# main.net
KiCad netlist of a schematic drawn in EAGLE
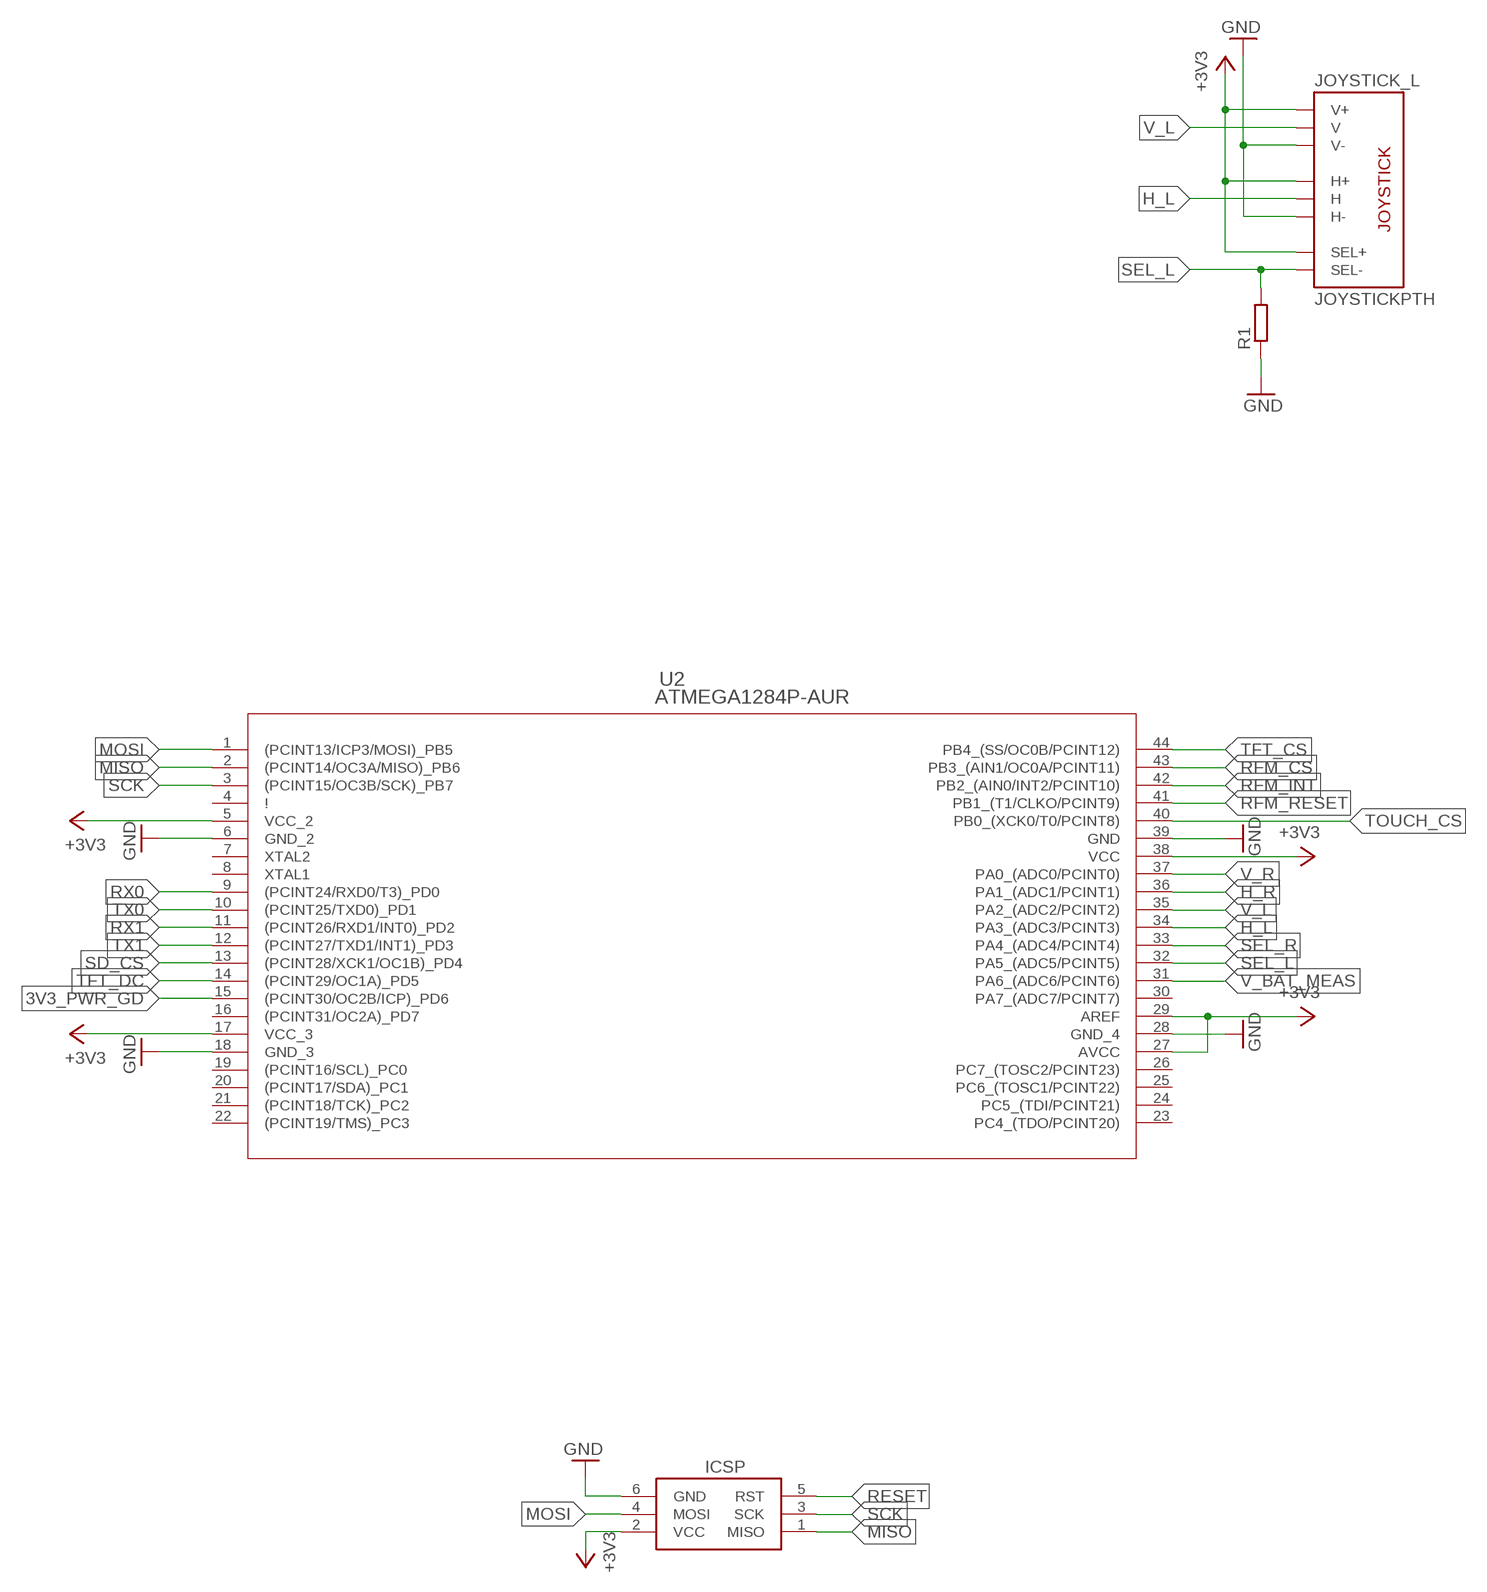
[diagram p0: schematic, sheet 1, part 1 of 2]
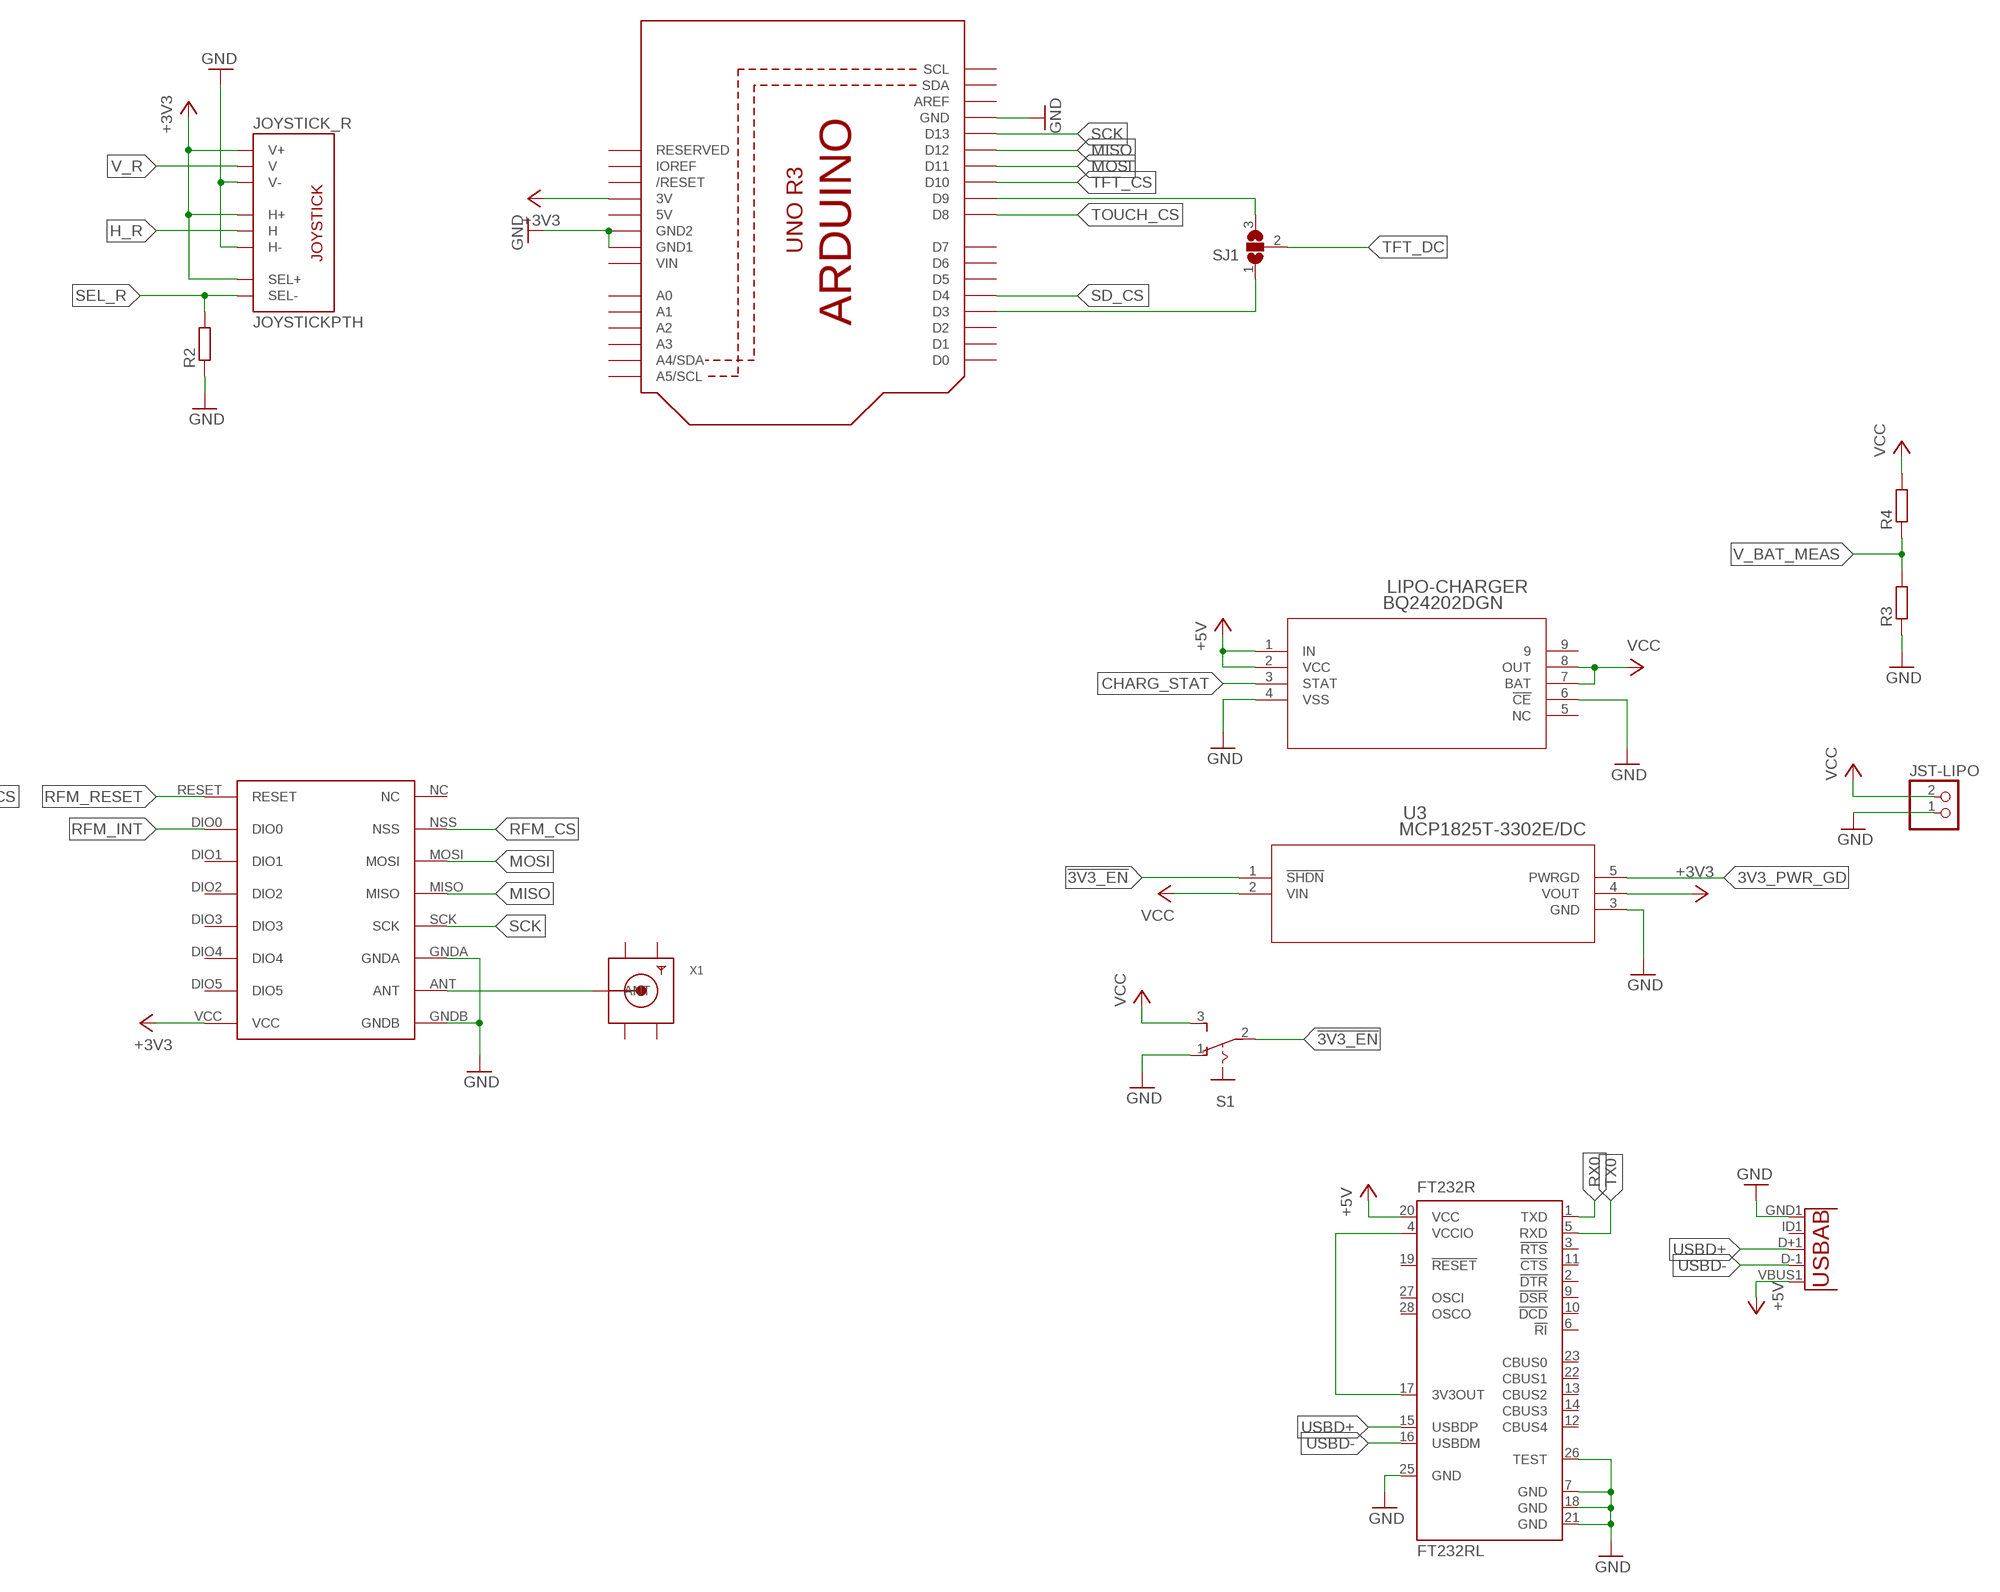
[diagram p1: schematic, sheet 1, part 2 of 2]

(export (version "E")
  (design (tool "Eeschema 10.0.6"))
  (components
    (comp (ref "FT232R")
      (value "FT232RL")
      (footprint "eagle-import:SSOP28")
      (libsource (lib "eagle-import") (part "FT232RL"))
    )
    (comp (ref "ICSP")
      (value "AVRISP-BOX")
      (footprint "eagle-import:AVRISP-BOX")
      (libsource (lib "eagle-import") (part "AVRISP-BOX"))
    )
    (comp (ref "JOYSTICK_L")
      (value "JOYSTICKPTH")
      (footprint "eagle-import:JOYSTICK")
      (libsource (lib "eagle-import") (part "JOYSTICKPTH"))
    )
    (comp (ref "JOYSTICK_R")
      (value "JOYSTICKPTH")
      (footprint "eagle-import:JOYSTICK")
      (libsource (lib "eagle-import") (part "JOYSTICKPTH"))
    )
    (comp (ref "JST-LIPO")
      (value "JST_2PIN-SMT-RA")
      (footprint "eagle-import:JST-PH-2-SMT-RA")
      (libsource (lib "eagle-import") (part "JST_2PIN-SMT-RA"))
    )
    (comp (ref "LCD")
      (value "ARDUINOR3-DIMENSION")
      (footprint "eagle-import:ARDUINOR3")
      (libsource (lib "eagle-import") (part "ARDUINOR3-DIMENSION"))
    )
    (comp (ref "LIPO-CHARGER")
      (value "BQ24202DGN")
      (footprint "eagle-import:DGN8")
      (libsource (lib "eagle-import") (part "BQ24202DGN"))
    )
    (comp (ref "R1")
      (value "R-EU_R1206")
      (footprint "eagle-import:R1206")
      (libsource (lib "eagle-import") (part "R-EU_R1206"))
    )
    (comp (ref "R2")
      (value "R-EU_R1206")
      (footprint "eagle-import:R1206")
      (libsource (lib "eagle-import") (part "R-EU_R1206"))
    )
    (comp (ref "R3")
      (value "R-EU_R1206")
      (footprint "eagle-import:R1206")
      (libsource (lib "eagle-import") (part "R-EU_R1206"))
    )
    (comp (ref "R4")
      (value "R-EU_R1206")
      (footprint "eagle-import:R1206")
      (libsource (lib "eagle-import") (part "R-EU_R1206"))
    )
    (comp (ref "RFM96W")
      (value "RFM69HW")
      (footprint "eagle-import:RFM")
      (libsource (lib "eagle-import") (part "RFM69HW"))
    )
    (comp (ref "S1")
      (value "255SB")
      (footprint "eagle-import:255SB")
      (libsource (lib "eagle-import") (part "255SB"))
    )
    (comp (ref "SJ1")
      (value "SJ2W")
      (footprint "eagle-import:SJ_2")
      (libsource (lib "eagle-import") (part "SJ2W"))
    )
    (comp (ref "U1")
      (value "USB\"\"")
      (footprint "eagle-import:USB-MICRO-SMD")
      (libsource (lib "eagle-import") (part "USB{dblquote}{dblquote}"))
    )
    (comp (ref "U2")
      (value "ATMEGA1284P-AUR")
      (footprint "eagle-import:44A")
      (fields (field (name "MANUFACTURER_PART_NUMBER") "ATMEGA1284PAUR"))
      (libsource (lib "eagle-import") (part "ATMEGA1284P-AUR"))
    )
    (comp (ref "U3")
      (value "MCP1825T-3302E/DC")
      (footprint "eagle-import:SOT-223_5MC")
      (fields (field (name "MANUFACTURER_PART_NUMBER") "MCP1825T3302EDC"))
      (libsource (lib "eagle-import") (part "MCP1825T-3302E/DC"))
    )
    (comp (ref "X1")
      (value "SMACONNECTOR_EDGE")
      (footprint "eagle-import:SMA_EDGELAUNCH")
      (libsource (lib "eagle-import") (part "SMACONNECTOR_EDGE"))
    )
  )
  (nets
    (net (code "1") (name "+3V3") (class "Default")
      (node (ref "ICSP") (pin "2") (pinfunction "VCC_2") (pintype "power_in"))
      (node (ref "JOYSTICK_L") (pin "B1A") (pinfunction "SEL+_B1A") (pintype "bidirectional"))
      (node (ref "JOYSTICK_L") (pin "H1") (pinfunction "H+_H1") (pintype "bidirectional"))
      (node (ref "JOYSTICK_L") (pin "V1") (pinfunction "V+_V1") (pintype "bidirectional"))
      (node (ref "JOYSTICK_R") (pin "B1A") (pinfunction "SEL+_B1A") (pintype "bidirectional"))
      (node (ref "JOYSTICK_R") (pin "H1") (pinfunction "H+_H1") (pintype "bidirectional"))
      (node (ref "JOYSTICK_R") (pin "V1") (pinfunction "V+_V1") (pintype "bidirectional"))
      (node (ref "LCD") (pin "3V") (pinfunction "3V_3V") (pintype "power_in"))
      (node (ref "RFM96W") (pin "VCC") (pinfunction "VCC_VCC") (pintype "bidirectional"))
      (node (ref "U2") (pin "17") (pinfunction "VCC_3_17") (pintype "power_in"))
      (node (ref "U2") (pin "27") (pinfunction "AVCC_27") (pintype "power_in"))
      (node (ref "U2") (pin "29") (pinfunction "AREF_29") (pintype "passive"))
      (node (ref "U2") (pin "38") (pinfunction "VCC_38") (pintype "power_in"))
      (node (ref "U2") (pin "5") (pinfunction "VCC_2_5") (pintype "power_in"))
      (node (ref "U3") (pin "4") (pinfunction "VOUT_4") (pintype "passive"))
    )
    (net (code "2") (name "+5V") (class "Default")
      (node (ref "FT232R") (pin "20") (pinfunction "VCC_20") (pintype "power_in"))
      (node (ref "LIPO-CHARGER") (pin "1") (pinfunction "IN_1") (pintype "input"))
      (node (ref "LIPO-CHARGER") (pin "2") (pinfunction "VCC_2") (pintype "power_in"))
      (node (ref "U1") (pin "VBUS1") (pinfunction "VBUS_VBUS1") (pintype "bidirectional"))
    )
    (net (code "3") (name "3V3_PWR_GD") (class "Default")
      (node (ref "U2") (pin "15") (pinfunction "(PCINT30/OC2B/ICP)_PD6_15") (pintype "bidirectional"))
      (node (ref "U3") (pin "5") (pinfunction "PWRGD_5") (pintype "passive"))
    )
    (net (code "4") (name "5V") (class "Default")
      (node (ref "LCD") (pin "5V") (pinfunction "5V_5V") (pintype "power_in"))
    )
    (net (code "5") (name "CHARG_STAT") (class "Default")
      (node (ref "LIPO-CHARGER") (pin "3") (pinfunction "STAT_3") (pintype "output"))
    )
    (net (code "6") (name "GND") (class "Default")
      (node (ref "FT232R") (pin "18") (pinfunction "GND_18") (pintype "power_in"))
      (node (ref "FT232R") (pin "21") (pinfunction "GND_21") (pintype "power_in"))
      (node (ref "FT232R") (pin "25") (pinfunction "GND_25") (pintype "power_in"))
      (node (ref "FT232R") (pin "26") (pinfunction "TEST_26") (pintype "input"))
      (node (ref "FT232R") (pin "7") (pinfunction "GND_7") (pintype "power_in"))
      (node (ref "ICSP") (pin "6") (pinfunction "GND_6") (pintype "power_in"))
      (node (ref "JOYSTICK_L") (pin "H3") (pinfunction "H-_H3") (pintype "bidirectional"))
      (node (ref "JOYSTICK_L") (pin "V3") (pinfunction "V-_V3") (pintype "bidirectional"))
      (node (ref "JOYSTICK_R") (pin "H3") (pinfunction "H-_H3") (pintype "bidirectional"))
      (node (ref "JOYSTICK_R") (pin "V3") (pinfunction "V-_V3") (pintype "bidirectional"))
      (node (ref "JST-LIPO") (pin "1") (pinfunction "2_1") (pintype "passive"))
      (node (ref "LCD") (pin "GND") (pinfunction "GND_GND") (pintype "power_in"))
      (node (ref "LCD") (pin "GND1") (pinfunction "GND1_GND1") (pintype "power_in"))
      (node (ref "LCD") (pin "GND2") (pinfunction "GND2_GND2") (pintype "power_in"))
      (node (ref "LIPO-CHARGER") (pin "4") (pinfunction "VSS_4") (pintype "power_in"))
      (node (ref "LIPO-CHARGER") (pin "6") (pinfunction "~{CE}_6") (pintype "input"))
      (node (ref "R1") (pin "1") (pinfunction "1_1") (pintype "passive"))
      (node (ref "R2") (pin "1") (pinfunction "1_1") (pintype "passive"))
      (node (ref "R3") (pin "1") (pinfunction "1_1") (pintype "passive"))
      (node (ref "RFM96W") (pin "GNDA") (pinfunction "GNDA_GNDA") (pintype "bidirectional"))
      (node (ref "RFM96W") (pin "GNDB") (pinfunction "GNDB_GNDB") (pintype "bidirectional"))
      (node (ref "S1") (pin "1") (pinfunction "O_1") (pintype "passive"))
      (node (ref "U1") (pin "GND1") (pinfunction "GND_GND1") (pintype "bidirectional"))
      (node (ref "U2") (pin "18") (pinfunction "GND_3_18") (pintype "power_in"))
      (node (ref "U2") (pin "28") (pinfunction "GND_4_28") (pintype "power_in"))
      (node (ref "U2") (pin "39") (pinfunction "GND_39") (pintype "power_in"))
      (node (ref "U2") (pin "6") (pinfunction "GND_2_6") (pintype "power_in"))
      (node (ref "U3") (pin "3") (pinfunction "GND_3") (pintype "passive"))
    )
    (net (code "7") (name "GND1") (class "Default")
      (node (ref "X1") (pin "GND@4") (pinfunction "GND1_GND@4") (pintype "power_in"))
    )
    (net (code "8") (name "GND2") (class "Default")
      (node (ref "X1") (pin "GND@3") (pinfunction "GND2_GND@3") (pintype "power_in"))
    )
    (net (code "9") (name "GND3") (class "Default")
      (node (ref "X1") (pin "GND@2") (pinfunction "GND3_GND@2") (pintype "power_in"))
    )
    (net (code "10") (name "GND4") (class "Default")
      (node (ref "X1") (pin "GND@1") (pinfunction "GND4_GND@1") (pintype "power_in"))
    )
    (net (code "11") (name "H_L") (class "Default")
      (node (ref "JOYSTICK_L") (pin "H2") (pinfunction "H_H2") (pintype "bidirectional"))
      (node (ref "U2") (pin "34") (pinfunction "PA3_(ADC3/PCINT3)_34") (pintype "bidirectional"))
    )
    (net (code "12") (name "H_R") (class "Default")
      (node (ref "JOYSTICK_R") (pin "H2") (pinfunction "H_H2") (pintype "bidirectional"))
      (node (ref "U2") (pin "36") (pinfunction "PA1_(ADC1/PCINT1)_36") (pintype "bidirectional"))
    )
    (net (code "13") (name "MISO") (class "Default")
      (node (ref "ICSP") (pin "1") (pinfunction "MISO_1") (pintype "input"))
      (node (ref "LCD") (pin "D12") (pinfunction "D12_D12") (pintype "bidirectional"))
      (node (ref "RFM96W") (pin "MISO") (pinfunction "MISO_MISO") (pintype "bidirectional"))
      (node (ref "U2") (pin "2") (pinfunction "(PCINT14/OC3A/MISO)_PB6_2") (pintype "bidirectional"))
    )
    (net (code "14") (name "MOSI") (class "Default")
      (node (ref "ICSP") (pin "4") (pinfunction "MOSI_4") (pintype "output"))
      (node (ref "LCD") (pin "D11") (pinfunction "D11_D11") (pintype "bidirectional"))
      (node (ref "RFM96W") (pin "MOSI") (pinfunction "MOSI_MOSI") (pintype "bidirectional"))
      (node (ref "U2") (pin "1") (pinfunction "(PCINT13/ICP3/MOSI)_PB5_1") (pintype "bidirectional"))
    )
    (net (code "15") (name "Net-(FT232R-3V3OUT)") (class "Default")
      (node (ref "FT232R") (pin "17") (pinfunction "3V3OUT_17") (pintype "output"))
      (node (ref "FT232R") (pin "4") (pinfunction "VCCIO_4") (pintype "power_in"))
    )
    (net (code "16") (name "Net-(LCD-PadD3)") (class "Default")
      (node (ref "LCD") (pin "D3") (pinfunction "D3_D3") (pintype "bidirectional"))
      (node (ref "SJ1") (pin "1") (pinfunction "1_1") (pintype "passive"))
    )
    (net (code "17") (name "Net-(LCD-PadD9)") (class "Default")
      (node (ref "LCD") (pin "D9") (pinfunction "D9_D9") (pintype "bidirectional"))
      (node (ref "SJ1") (pin "3") (pinfunction "3_3") (pintype "passive"))
    )
    (net (code "18") (name "Net-(X1-ANT)") (class "Default")
      (node (ref "RFM96W") (pin "ANT") (pinfunction "ANT_ANT") (pintype "bidirectional"))
      (node (ref "X1") (pin "P") (pinfunction "ANT_P") (pintype "bidirectional"))
    )
    (net (code "19") (name "RESET") (class "Default")
      (node (ref "ICSP") (pin "5") (pinfunction "RST_5") (pintype "output"))
    )
    (net (code "20") (name "RFM_CS") (class "Default")
      (node (ref "RFM96W") (pin "NSS") (pinfunction "NSS_NSS") (pintype "bidirectional"))
      (node (ref "U2") (pin "43") (pinfunction "PB3_(AIN1/OC0A/PCINT11)_43") (pintype "bidirectional"))
    )
    (net (code "21") (name "RFM_INT") (class "Default")
      (node (ref "RFM96W") (pin "DIO0") (pinfunction "DIO0_DIO0") (pintype "bidirectional"))
      (node (ref "U2") (pin "42") (pinfunction "PB2_(AIN0/INT2/PCINT10)_42") (pintype "bidirectional"))
    )
    (net (code "22") (name "RFM_RESET") (class "Default")
      (node (ref "RFM96W") (pin "RESET") (pinfunction "RESET_RESET") (pintype "bidirectional"))
      (node (ref "U2") (pin "41") (pinfunction "PB1_(T1/CLKO/PCINT9)_41") (pintype "bidirectional"))
    )
    (net (code "23") (name "RX0") (class "Default")
      (node (ref "FT232R") (pin "1") (pinfunction "TXD_1") (pintype "output"))
      (node (ref "U2") (pin "9") (pinfunction "(PCINT24/RXD0/T3)_PD0_9") (pintype "bidirectional"))
    )
    (net (code "24") (name "RX1") (class "Default")
      (node (ref "U2") (pin "11") (pinfunction "(PCINT26/RXD1/INT0)_PD2_11") (pintype "bidirectional"))
    )
    (net (code "25") (name "SCK") (class "Default")
      (node (ref "ICSP") (pin "3") (pinfunction "SCK_3") (pintype "output"))
      (node (ref "LCD") (pin "D13") (pinfunction "D13_D13") (pintype "bidirectional"))
      (node (ref "RFM96W") (pin "SCK") (pinfunction "SCK_SCK") (pintype "bidirectional"))
      (node (ref "U2") (pin "3") (pinfunction "(PCINT15/OC3B/SCK)_PB7_3") (pintype "bidirectional"))
    )
    (net (code "26") (name "SD_CS") (class "Default")
      (node (ref "LCD") (pin "D4") (pinfunction "D4_D4") (pintype "bidirectional"))
      (node (ref "U2") (pin "13") (pinfunction "(PCINT28/XCK1/OC1B)_PD4_13") (pintype "bidirectional"))
    )
    (net (code "27") (name "SEL_L") (class "Default")
      (node (ref "JOYSTICK_L") (pin "B2A") (pinfunction "SEL-_B2A") (pintype "bidirectional"))
      (node (ref "R1") (pin "2") (pinfunction "2_2") (pintype "passive"))
      (node (ref "U2") (pin "32") (pinfunction "PA5_(ADC5/PCINT5)_32") (pintype "bidirectional"))
    )
    (net (code "28") (name "SEL_R") (class "Default")
      (node (ref "JOYSTICK_R") (pin "B2A") (pinfunction "SEL-_B2A") (pintype "bidirectional"))
      (node (ref "R2") (pin "2") (pinfunction "2_2") (pintype "passive"))
      (node (ref "U2") (pin "33") (pinfunction "PA4_(ADC4/PCINT4)_33") (pintype "bidirectional"))
    )
    (net (code "29") (name "TFT_CS") (class "Default")
      (node (ref "LCD") (pin "D10") (pinfunction "D10_D10") (pintype "bidirectional"))
      (node (ref "U2") (pin "44") (pinfunction "PB4_(SS/OC0B/PCINT12)_44") (pintype "bidirectional"))
    )
    (net (code "30") (name "TFT_DC") (class "Default")
      (node (ref "SJ1") (pin "2") (pinfunction "2_2") (pintype "passive"))
      (node (ref "U2") (pin "14") (pinfunction "(PCINT29/OC1A)_PD5_14") (pintype "bidirectional"))
    )
    (net (code "31") (name "TOUCH_CS") (class "Default")
      (node (ref "LCD") (pin "D8") (pinfunction "D8_D8") (pintype "bidirectional"))
      (node (ref "U2") (pin "40") (pinfunction "PB0_(XCK0/T0/PCINT8)_40") (pintype "bidirectional"))
    )
    (net (code "32") (name "TX0") (class "Default")
      (node (ref "FT232R") (pin "5") (pinfunction "RXD_5") (pintype "input"))
      (node (ref "U2") (pin "10") (pinfunction "(PCINT25/TXD0)_PD1_10") (pintype "bidirectional"))
    )
    (net (code "33") (name "TX1") (class "Default")
      (node (ref "U2") (pin "12") (pinfunction "(PCINT27/TXD1/INT1)_PD3_12") (pintype "bidirectional"))
    )
    (net (code "34") (name "USBD+") (class "Default")
      (node (ref "FT232R") (pin "15") (pinfunction "USBDP_15") (pintype "bidirectional"))
      (node (ref "U1") (pin "D+1") (pinfunction "D+_D+1") (pintype "bidirectional"))
    )
    (net (code "35") (name "USBD-") (class "Default")
      (node (ref "FT232R") (pin "16") (pinfunction "USBDM_16") (pintype "bidirectional"))
      (node (ref "U1") (pin "D-1") (pinfunction "D-_D-1") (pintype "bidirectional"))
    )
    (net (code "36") (name "VCC") (class "Default")
      (node (ref "JST-LIPO") (pin "2") (pinfunction "1_2") (pintype "passive"))
      (node (ref "LIPO-CHARGER") (pin "7") (pinfunction "BAT_7") (pintype "input"))
      (node (ref "LIPO-CHARGER") (pin "8") (pinfunction "OUT_8") (pintype "output"))
      (node (ref "R4") (pin "2") (pinfunction "2_2") (pintype "passive"))
      (node (ref "S1") (pin "3") (pinfunction "S_3") (pintype "passive"))
      (node (ref "U3") (pin "2") (pinfunction "VIN_2") (pintype "passive"))
    )
    (net (code "37") (name "VIN") (class "Default")
      (node (ref "LCD") (pin "VIN") (pinfunction "VIN_VIN") (pintype "power_in"))
    )
    (net (code "38") (name "V_BAT_MEAS") (class "Default")
      (node (ref "R3") (pin "2") (pinfunction "2_2") (pintype "passive"))
      (node (ref "R4") (pin "1") (pinfunction "1_1") (pintype "passive"))
      (node (ref "U2") (pin "31") (pinfunction "PA6_(ADC6/PCINT6)_31") (pintype "bidirectional"))
    )
    (net (code "39") (name "V_L") (class "Default")
      (node (ref "JOYSTICK_L") (pin "V2") (pinfunction "V_V2") (pintype "bidirectional"))
      (node (ref "U2") (pin "35") (pinfunction "PA2_(ADC2/PCINT2)_35") (pintype "bidirectional"))
    )
    (net (code "40") (name "V_R") (class "Default")
      (node (ref "JOYSTICK_R") (pin "V2") (pinfunction "V_V2") (pintype "bidirectional"))
      (node (ref "U2") (pin "37") (pinfunction "PA0_(ADC0/PCINT0)_37") (pintype "bidirectional"))
    )
    (net (code "41") (name "unconnected-(FT232R-CBUS0-Pad23)") (class "Default")
      (node (ref "FT232R") (pin "23") (pinfunction "CBUS0_23") (pintype "bidirectional"))
    )
    (net (code "42") (name "unconnected-(FT232R-CBUS1-Pad22)") (class "Default")
      (node (ref "FT232R") (pin "22") (pinfunction "CBUS1_22") (pintype "bidirectional"))
    )
    (net (code "43") (name "unconnected-(FT232R-CBUS2-Pad13)") (class "Default")
      (node (ref "FT232R") (pin "13") (pinfunction "CBUS2_13") (pintype "bidirectional"))
    )
    (net (code "44") (name "unconnected-(FT232R-CBUS3-Pad14)") (class "Default")
      (node (ref "FT232R") (pin "14") (pinfunction "CBUS3_14") (pintype "bidirectional"))
    )
    (net (code "45") (name "unconnected-(FT232R-CBUS4-Pad12)") (class "Default")
      (node (ref "FT232R") (pin "12") (pinfunction "CBUS4_12") (pintype "bidirectional"))
    )
    (net (code "46") (name "unconnected-(FT232R-OSCI-Pad27)") (class "Default")
      (node (ref "FT232R") (pin "27") (pinfunction "OSCI_27") (pintype "input"))
    )
    (net (code "47") (name "unconnected-(FT232R-OSCO-Pad28)") (class "Default")
      (node (ref "FT232R") (pin "28") (pinfunction "OSCO_28") (pintype "output"))
    )
    (net (code "48") (name "unconnected-(FT232R-~{CTS}-Pad11)") (class "Default")
      (node (ref "FT232R") (pin "11") (pinfunction "~{CTS}_11") (pintype "input"))
    )
    (net (code "49") (name "unconnected-(FT232R-~{DCD}-Pad10)") (class "Default")
      (node (ref "FT232R") (pin "10") (pinfunction "~{DCD}_10") (pintype "input"))
    )
    (net (code "50") (name "unconnected-(FT232R-~{DSR}-Pad9)") (class "Default")
      (node (ref "FT232R") (pin "9") (pinfunction "~{DSR}_9") (pintype "input"))
    )
    (net (code "51") (name "unconnected-(FT232R-~{DTR}-Pad2)") (class "Default")
      (node (ref "FT232R") (pin "2") (pinfunction "~{DTR}_2") (pintype "output"))
    )
    (net (code "52") (name "unconnected-(FT232R-~{RESET}-Pad19)") (class "Default")
      (node (ref "FT232R") (pin "19") (pinfunction "~{RESET}_19") (pintype "input"))
    )
    (net (code "53") (name "unconnected-(FT232R-~{RI}-Pad6)") (class "Default")
      (node (ref "FT232R") (pin "6") (pinfunction "~{RI}_6") (pintype "input"))
    )
    (net (code "54") (name "unconnected-(FT232R-~{RTS}-Pad3)") (class "Default")
      (node (ref "FT232R") (pin "3") (pinfunction "~{RTS}_3") (pintype "output"))
    )
    (net (code "55") (name "unconnected-(LCD-A4{slash}SDA-PadA4)") (class "Default")
      (node (ref "LCD") (pin "A4") (pinfunction "A4/SDA_A4") (pintype "bidirectional"))
    )
    (net (code "56") (name "unconnected-(LCD-A5{slash}SCL-PadA5)") (class "Default")
      (node (ref "LCD") (pin "A5") (pinfunction "A5/SCL_A5") (pintype "bidirectional"))
    )
    (net (code "57") (name "unconnected-(LCD-PadA0)") (class "Default")
      (node (ref "LCD") (pin "A0") (pinfunction "A0_A0") (pintype "bidirectional"))
    )
    (net (code "58") (name "unconnected-(LCD-PadA1)") (class "Default")
      (node (ref "LCD") (pin "A1") (pinfunction "A1_A1") (pintype "bidirectional"))
    )
    (net (code "59") (name "unconnected-(LCD-PadA2)") (class "Default")
      (node (ref "LCD") (pin "A2") (pinfunction "A2_A2") (pintype "bidirectional"))
    )
    (net (code "60") (name "unconnected-(LCD-PadA3)") (class "Default")
      (node (ref "LCD") (pin "A3") (pinfunction "A3_A3") (pintype "bidirectional"))
    )
    (net (code "61") (name "unconnected-(LCD-PadAREF)") (class "Default")
      (node (ref "LCD") (pin "AREF") (pinfunction "AREF_AREF") (pintype "bidirectional"))
    )
    (net (code "62") (name "unconnected-(LCD-PadD0)") (class "Default")
      (node (ref "LCD") (pin "D0") (pinfunction "D0_D0") (pintype "bidirectional"))
    )
    (net (code "63") (name "unconnected-(LCD-PadD1)") (class "Default")
      (node (ref "LCD") (pin "D1") (pinfunction "D1_D1") (pintype "bidirectional"))
    )
    (net (code "64") (name "unconnected-(LCD-PadD2)") (class "Default")
      (node (ref "LCD") (pin "D2") (pinfunction "D2_D2") (pintype "bidirectional"))
    )
    (net (code "65") (name "unconnected-(LCD-PadD5)") (class "Default")
      (node (ref "LCD") (pin "D5") (pinfunction "D5_D5") (pintype "bidirectional"))
    )
    (net (code "66") (name "unconnected-(LCD-PadD6)") (class "Default")
      (node (ref "LCD") (pin "D6") (pinfunction "D6_D6") (pintype "bidirectional"))
    )
    (net (code "67") (name "unconnected-(LCD-PadD7)") (class "Default")
      (node (ref "LCD") (pin "D7") (pinfunction "D7_D7") (pintype "bidirectional"))
    )
    (net (code "68") (name "unconnected-(LCD-PadIOREF)") (class "Default")
      (node (ref "LCD") (pin "IOREF") (pinfunction "IOREF_IOREF") (pintype "output"))
    )
    (net (code "69") (name "unconnected-(LCD-PadRESERVED)") (class "Default")
      (node (ref "LCD") (pin "RESERVED") (pinfunction "RESERVED_RESERVED") (pintype "no_connect"))
    )
    (net (code "70") (name "unconnected-(LCD-PadSCL)") (class "Default")
      (node (ref "LCD") (pin "SCL") (pinfunction "SCL_SCL") (pintype "bidirectional"))
    )
    (net (code "71") (name "unconnected-(LCD-PadSDA)") (class "Default")
      (node (ref "LCD") (pin "SDA") (pinfunction "SDA_SDA") (pintype "bidirectional"))
    )
    (net (code "72") (name "unconnected-(LCD-{slash}RESET-PadRESET)") (class "Default")
      (node (ref "LCD") (pin "RESET") (pinfunction "/RESET_RESET") (pintype "bidirectional"))
    )
    (net (code "73") (name "unconnected-(LIPO-CHARGER-NC-Pad5)") (class "Default")
      (node (ref "LIPO-CHARGER") (pin "5") (pinfunction "NC_5") (pintype "no_connect"))
    )
    (net (code "74") (name "unconnected-(LIPO-CHARGER-Pad9)") (class "Default")
      (node (ref "LIPO-CHARGER") (pin "9") (pinfunction "9_9") (pintype "passive"))
    )
    (net (code "75") (name "unconnected-(RFM96W-PadDIO1)") (class "Default")
      (node (ref "RFM96W") (pin "DIO1") (pinfunction "DIO1_DIO1") (pintype "bidirectional"))
    )
    (net (code "76") (name "unconnected-(RFM96W-PadDIO2)") (class "Default")
      (node (ref "RFM96W") (pin "DIO2") (pinfunction "DIO2_DIO2") (pintype "bidirectional"))
    )
    (net (code "77") (name "unconnected-(RFM96W-PadDIO3)") (class "Default")
      (node (ref "RFM96W") (pin "DIO3") (pinfunction "DIO3_DIO3") (pintype "bidirectional"))
    )
    (net (code "78") (name "unconnected-(RFM96W-PadDIO4)") (class "Default")
      (node (ref "RFM96W") (pin "DIO4") (pinfunction "DIO4_DIO4") (pintype "bidirectional"))
    )
    (net (code "79") (name "unconnected-(RFM96W-PadDIO5)") (class "Default")
      (node (ref "RFM96W") (pin "DIO5") (pinfunction "DIO5_DIO5") (pintype "bidirectional"))
    )
    (net (code "80") (name "unconnected-(RFM96W-PadNC)") (class "Default")
      (node (ref "RFM96W") (pin "NC") (pinfunction "NC_NC") (pintype "bidirectional"))
    )
    (net (code "81") (name "unconnected-(U1-USBID-PadID1)") (class "Default")
      (node (ref "U1") (pin "ID1") (pinfunction "USBID_ID1") (pintype "bidirectional"))
    )
    (net (code "82") (name "unconnected-(U2-(PCINT16{slash}SCL)_PC0-Pad19)") (class "Default")
      (node (ref "U2") (pin "19") (pinfunction "(PCINT16/SCL)_PC0_19") (pintype "bidirectional"))
    )
    (net (code "83") (name "unconnected-(U2-(PCINT17{slash}SDA)_PC1-Pad20)") (class "Default")
      (node (ref "U2") (pin "20") (pinfunction "(PCINT17/SDA)_PC1_20") (pintype "bidirectional"))
    )
    (net (code "84") (name "unconnected-(U2-(PCINT18{slash}TCK)_PC2-Pad21)") (class "Default")
      (node (ref "U2") (pin "21") (pinfunction "(PCINT18/TCK)_PC2_21") (pintype "bidirectional"))
    )
    (net (code "85") (name "unconnected-(U2-(PCINT19{slash}TMS)_PC3-Pad22)") (class "Default")
      (node (ref "U2") (pin "22") (pinfunction "(PCINT19/TMS)_PC3_22") (pintype "bidirectional"))
    )
    (net (code "86") (name "unconnected-(U2-(PCINT31{slash}OC2A)_PD7-Pad16)") (class "Default")
      (node (ref "U2") (pin "16") (pinfunction "(PCINT31/OC2A)_PD7_16") (pintype "bidirectional"))
    )
    (net (code "87") (name "unconnected-(U2-PA7_(ADC7{slash}PCINT7)-Pad30)") (class "Default")
      (node (ref "U2") (pin "30") (pinfunction "PA7_(ADC7/PCINT7)_30") (pintype "bidirectional"))
    )
    (net (code "88") (name "unconnected-(U2-PC4_(TDO{slash}PCINT20)-Pad23)") (class "Default")
      (node (ref "U2") (pin "23") (pinfunction "PC4_(TDO/PCINT20)_23") (pintype "bidirectional"))
    )
    (net (code "89") (name "unconnected-(U2-PC5_(TDI{slash}PCINT21)-Pad24)") (class "Default")
      (node (ref "U2") (pin "24") (pinfunction "PC5_(TDI/PCINT21)_24") (pintype "bidirectional"))
    )
    (net (code "90") (name "unconnected-(U2-PC6_(TOSC1{slash}PCINT22)-Pad25)") (class "Default")
      (node (ref "U2") (pin "25") (pinfunction "PC6_(TOSC1/PCINT22)_25") (pintype "bidirectional"))
    )
    (net (code "91") (name "unconnected-(U2-PC7_(TOSC2{slash}PCINT23)-Pad26)") (class "Default")
      (node (ref "U2") (pin "26") (pinfunction "PC7_(TOSC2/PCINT23)_26") (pintype "bidirectional"))
    )
    (net (code "92") (name "unconnected-(U2-XTAL1-Pad8)") (class "Default")
      (node (ref "U2") (pin "8") (pinfunction "XTAL1_8") (pintype "input"))
    )
    (net (code "93") (name "unconnected-(U2-XTAL2-Pad7)") (class "Default")
      (node (ref "U2") (pin "7") (pinfunction "XTAL2_7") (pintype "passive"))
    )
    (net (code "94") (name "unconnected-(U2-~-Pad4)") (class "Default")
      (node (ref "U2") (pin "4") (pinfunction "~_4") (pintype "input"))
    )
    (net (code "95") (name "~{3V3_EN}") (class "Default")
      (node (ref "S1") (pin "2") (pinfunction "P_2") (pintype "passive"))
      (node (ref "U3") (pin "1") (pinfunction "~{SHDN}_1") (pintype "passive"))
    )
  )
)
